# Bears_and_Bears_BLE_soil_Moisture_Sensor.net
KiCad netlist of a schematic drawn in EAGLE
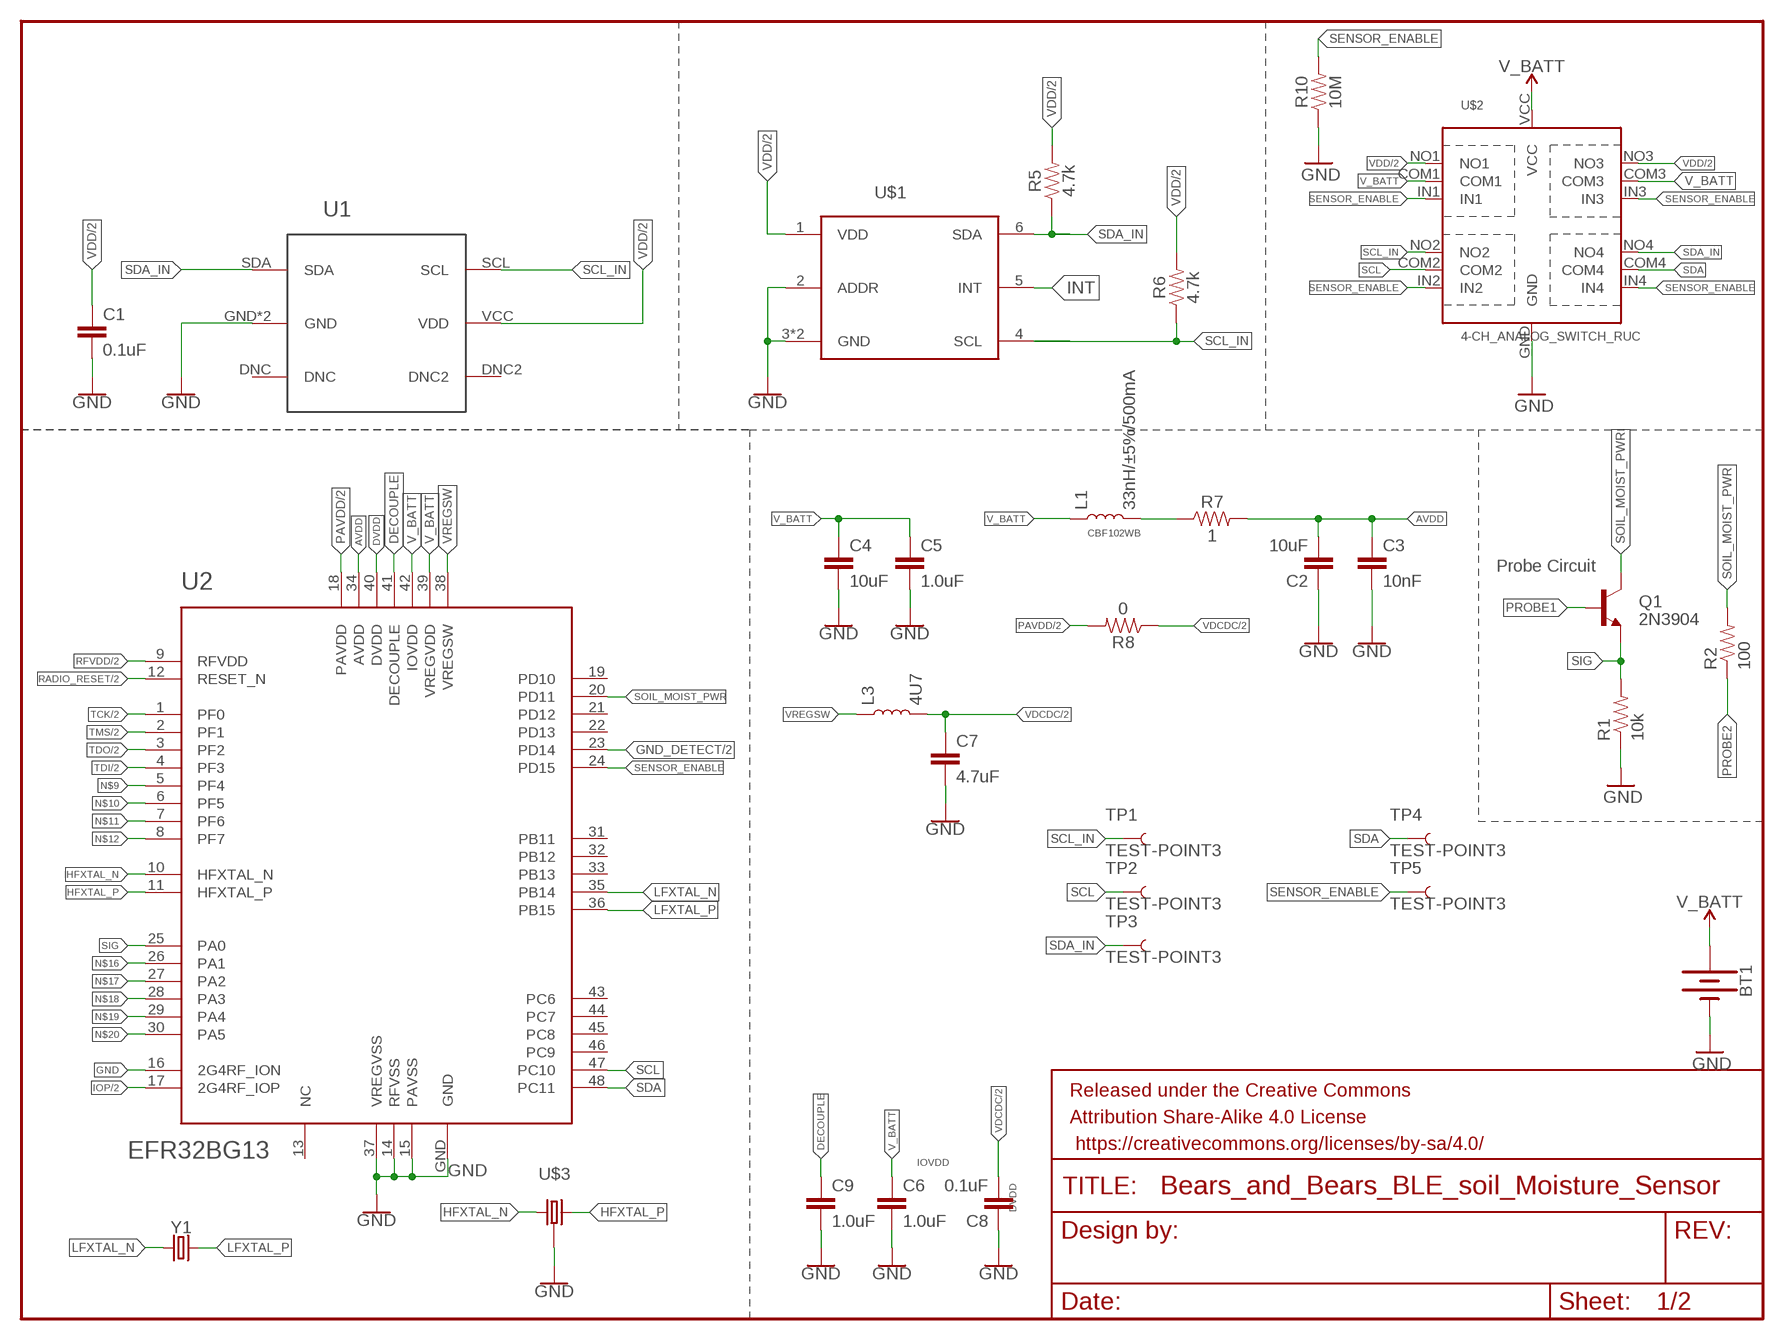
[diagram p0: schematic, sheet 1]
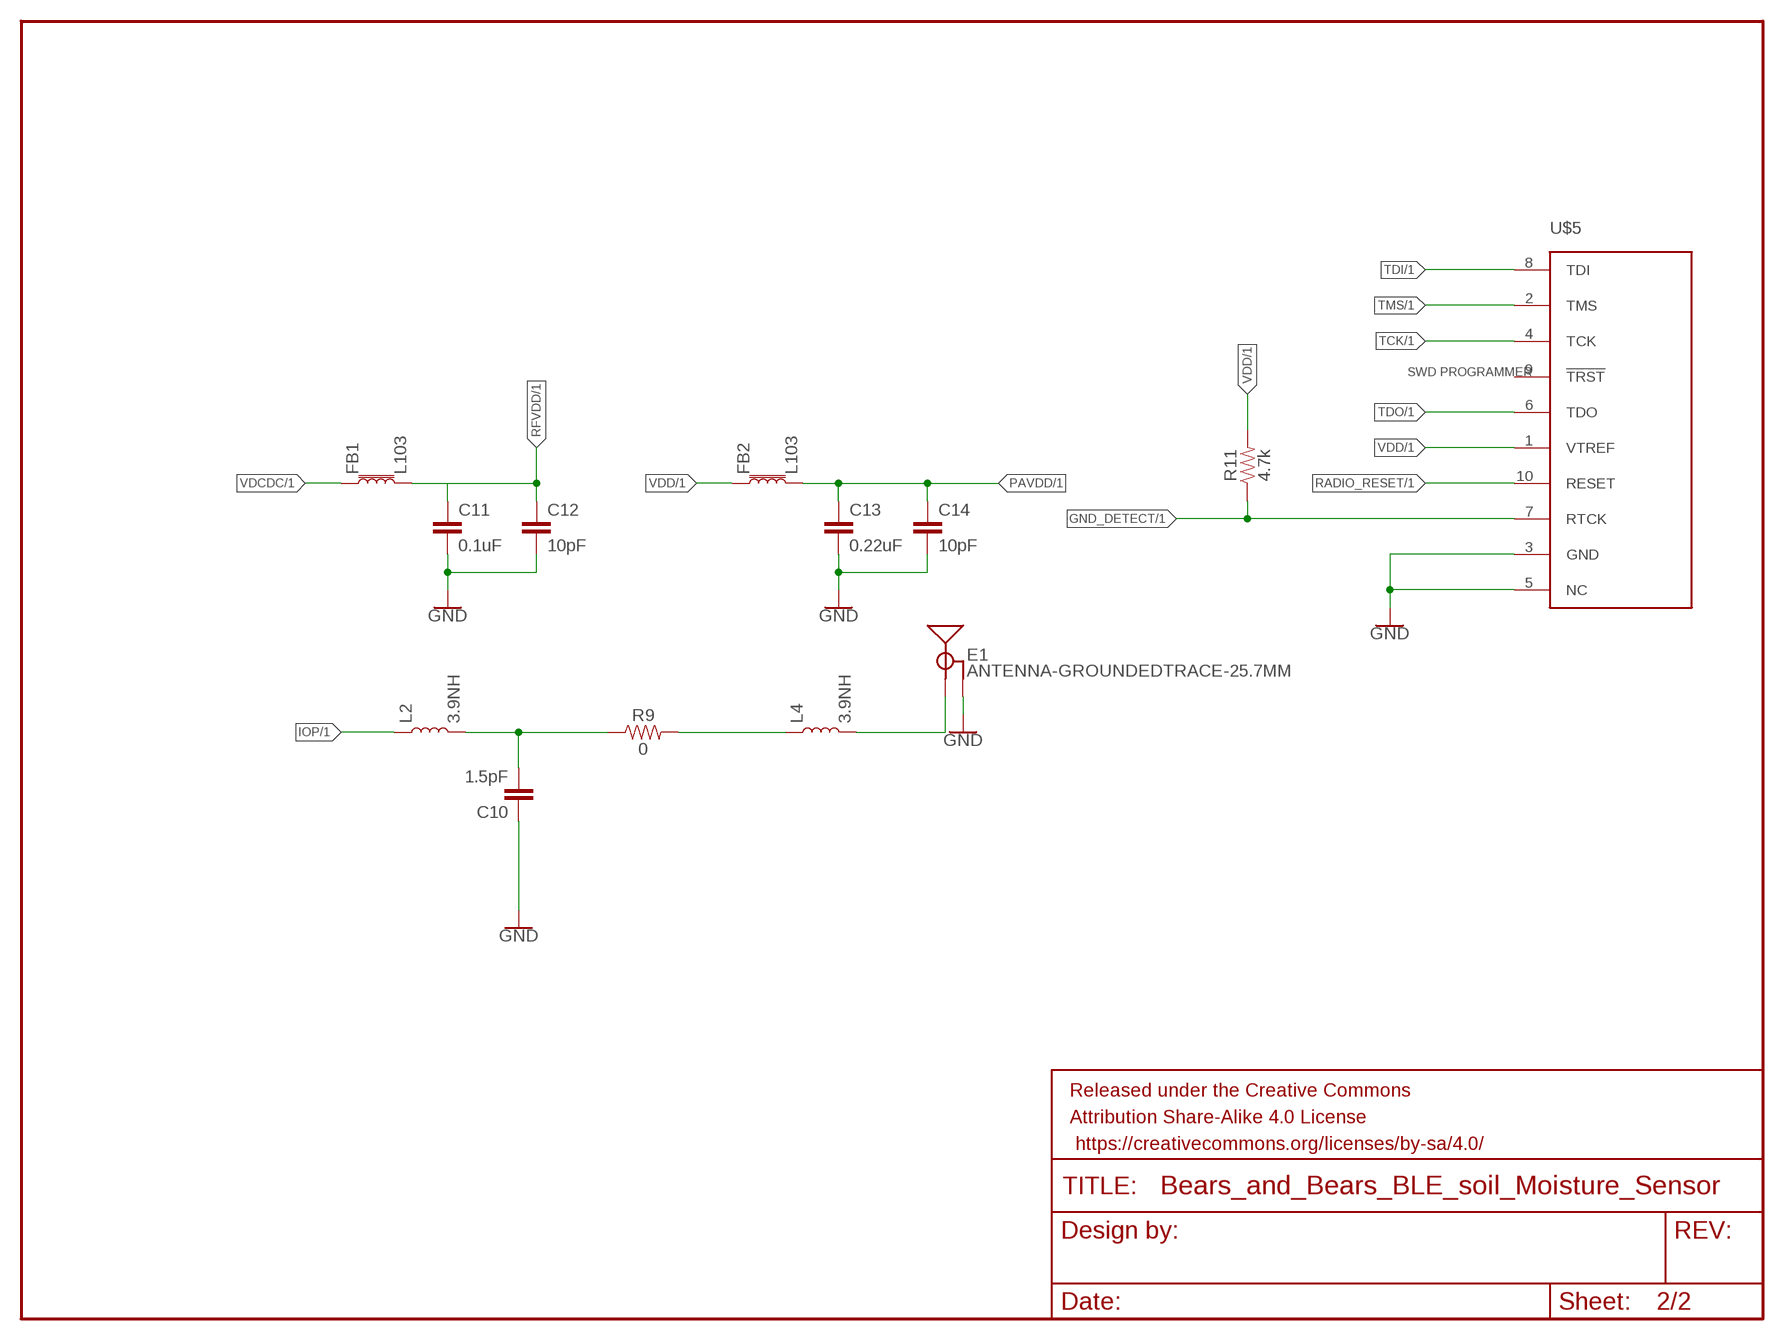
[diagram p1: schematic, sheet 2]

(export (version "E")
  (design (tool "Eeschema 10.0.6"))
  (components
    (comp (ref "BT1")
      (value "BATTERY-20MM_SMD_4LEGS_OVERPASTE")
      (footprint "eagle-import:BATTCON_20MM_4LEGS_OVERPASTE")
      (libsource (lib "eagle-import") (part "BATTERY-20MM_SMD_4LEGS_OVERPASTE"))
    )
    (comp (ref "C1")
      (value "0.1uF")
      (footprint "eagle-import:0603")
      (libsource (lib "eagle-import") (part "0.1UF-0603-25V-(+80/-20%)"))
    )
    (comp (ref "C2")
      (value "10uF")
      (footprint "eagle-import:0603")
      (libsource (lib "eagle-import") (part "10UF-0603-6.3V-20%"))
    )
    (comp (ref "C3")
      (value "10nF")
      (footprint "eagle-import:0603")
      (libsource (lib "eagle-import") (part "10NF-0603-50V-10%"))
    )
    (comp (ref "C4")
      (value "10uF")
      (footprint "eagle-import:0603")
      (libsource (lib "eagle-import") (part "10UF-0603-6.3V-20%"))
    )
    (comp (ref "C5")
      (value "1.0uF")
      (footprint "eagle-import:0603")
      (libsource (lib "eagle-import") (part "1.0UF-0603-16V-10%"))
    )
    (comp (ref "C6")
      (value "1.0uF")
      (footprint "eagle-import:0603")
      (libsource (lib "eagle-import") (part "1.0UF-0603-16V-10%"))
    )
    (comp (ref "C7")
      (value "4.7uF")
      (footprint "eagle-import:0603")
      (libsource (lib "eagle-import") (part "4.7UF0603"))
    )
    (comp (ref "C8")
      (value "0.1uF")
      (footprint "eagle-import:0603")
      (libsource (lib "eagle-import") (part "0.1UF-0603-25V-(+80/-20%)"))
    )
    (comp (ref "C9")
      (value "1.0uF")
      (footprint "eagle-import:0603")
      (libsource (lib "eagle-import") (part "1.0UF-0603-16V-10%"))
    )
    (comp (ref "FRAME1")
      (value "FRAME-LETTER")
      (footprint "eagle-import:CREATIVE_COMMONS")
      (libsource (lib "eagle-import") (part "FRAME-LETTER"))
    )
    (comp (ref "L1")
      (value "33nH/±5%/500mA")
      (footprint "eagle-import:0603")
      (libsource (lib "eagle-import") (part "INDUCTOR-0603-33NH"))
    )
    (comp (ref "L3")
      (value "4U7")
      (footprint "eagle-import:1212(3030METRIC)")
      (libsource (lib "eagle-import") (part "4U7"))
    )
    (comp (ref "Q1")
      (value "2N3904")
      (footprint "eagle-import:SOT23-3")
      (libsource (lib "eagle-import") (part "TRANSISTOR_NPNMMBT2222A"))
    )
    (comp (ref "R1")
      (value "10k")
      (footprint "eagle-import:0603-RES")
      (libsource (lib "eagle-import") (part "100OHM-1/4W-5%(0603)"))
    )
    (comp (ref "R2")
      (value "100")
      (footprint "eagle-import:0603-RES")
      (libsource (lib "eagle-import") (part "100OHM-1/4W-5%(0603)"))
    )
    (comp (ref "R5")
      (value "4.7k")
      (footprint "eagle-import:0603")
      (libsource (lib "eagle-import") (part "4.7KOHM-0603-1/10W-1%"))
    )
    (comp (ref "R6")
      (value "4.7k")
      (footprint "eagle-import:0603")
      (libsource (lib "eagle-import") (part "4.7KOHM-0603-1/10W-1%"))
    )
    (comp (ref "R7")
      (value "1")
      (footprint "eagle-import:0603")
      (libsource (lib "eagle-import") (part "1OHM-0603-1/10W-1%"))
    )
    (comp (ref "R8")
      (value "0")
      (footprint "eagle-import:0603")
      (libsource (lib "eagle-import") (part "0OHM-0603-1/10W-5%"))
    )
    (comp (ref "R10")
      (value "10M")
      (footprint "eagle-import:0603")
      (libsource (lib "eagle-import") (part "10MOHM-0603-1/10W-5%"))
    )
    (comp (ref "TP1")
      (value "TEST-POINT3")
      (footprint "eagle-import:PAD.03X.03")
      (libsource (lib "eagle-import") (part "TEST-POINT3"))
    )
    (comp (ref "TP2")
      (value "TEST-POINT3")
      (footprint "eagle-import:PAD.03X.03")
      (libsource (lib "eagle-import") (part "TEST-POINT3"))
    )
    (comp (ref "TP3")
      (value "TEST-POINT3")
      (footprint "eagle-import:PAD.03X.03")
      (libsource (lib "eagle-import") (part "TEST-POINT3"))
    )
    (comp (ref "TP4")
      (value "TEST-POINT3")
      (footprint "eagle-import:PAD.03X.03")
      (libsource (lib "eagle-import") (part "TEST-POINT3"))
    )
    (comp (ref "TP5")
      (value "TEST-POINT3")
      (footprint "eagle-import:PAD.03X.03")
      (libsource (lib "eagle-import") (part "TEST-POINT3"))
    )
    (comp (ref "U$1")
      (value "OPT3001DNPT")
      (footprint "eagle-import:6PIN_USON")
      (libsource (lib "eagle-import") (part "OPT3001DNPT"))
    )
    (comp (ref "U$2")
      (value "4-CH_ANALOG_SWITCH_RUC")
      (footprint "eagle-import:PX2QFN14_RUC")
      (libsource (lib "eagle-import") (part "4-CH_ANALOG_SWITCH_RUC"))
    )
    (comp (ref "U$3")
      (value "38.4MHZ_CRYSTAL")
      (footprint "eagle-import:2.0X1.6")
      (libsource (lib "eagle-import") (part "38.4MHZ_CRYSTAL"))
    )
    (comp (ref "U1")
      (value "SI7021_TEMP_HUMIDTY")
      (footprint "eagle-import:DFN-6")
      (libsource (lib "eagle-import") (part "SI7021_TEMP_HUMIDTY"))
    )
    (comp (ref "U2")
      (value "EFR32BG13")
      (footprint "eagle-import:QFN48")
      (libsource (lib "eagle-import") (part "EFR32BG13"))
    )
    (comp (ref "Y1")
      (value "32.768KHZ_LOW_FREQ_CRYSTAL")
      (footprint "eagle-import:CRYSTAL_1.2X0.6")
      (libsource (lib "eagle-import") (part "32.768KHZ_LOW_FREQ_CRYSTAL"))
    )
    (comp (ref "C10")
      (value "1.5pF")
      (footprint "eagle-import:0603")
      (libsource (lib "eagle-import") (part "1.5PF-0603-50V-16.667%"))
    )
    (comp (ref "C11")
      (value "0.1uF")
      (footprint "eagle-import:0603")
      (libsource (lib "eagle-import") (part "0.1UF-0603-25V-(+80/-20%)"))
    )
    (comp (ref "C12")
      (value "10pF")
      (footprint "eagle-import:0603")
      (libsource (lib "eagle-import") (part "10PF-0603-50V-5%"))
    )
    (comp (ref "C13")
      (value "0.22uF")
      (footprint "eagle-import:0603")
      (libsource (lib "eagle-import") (part "0.22UF-0603-25V-10%"))
    )
    (comp (ref "C14")
      (value "10pF")
      (footprint "eagle-import:0603")
      (libsource (lib "eagle-import") (part "10PF-0603-50V-5%"))
    )
    (comp (ref "E1")
      (value "ANTENNA-GROUNDEDTRACE-25.7MM")
      (footprint "eagle-import:TRACE_ANTENNA_2.4GHZ_25.7MM")
      (libsource (lib "eagle-import") (part "ANTENNA-GROUNDEDTRACE-25.7MM"))
    )
    (comp (ref "FB1")
      (value "L103")
      (footprint "eagle-import:0603")
      (libsource (lib "eagle-import") (part "FERRITE_BEAD-0603"))
    )
    (comp (ref "FB2")
      (value "L103")
      (footprint "eagle-import:0603")
      (libsource (lib "eagle-import") (part "FERRITE_BEAD-0603"))
    )
    (comp (ref "FRAME2")
      (value "FRAME-LETTER")
      (footprint "eagle-import:CREATIVE_COMMONS")
      (libsource (lib "eagle-import") (part "FRAME-LETTER"))
    )
    (comp (ref "L2")
      (value "3.9NH")
      (footprint "eagle-import:0402")
      (libsource (lib "eagle-import") (part "INDUCTOR-0402-3.9NH"))
    )
    (comp (ref "L4")
      (value "3.9NH")
      (footprint "eagle-import:0402")
      (libsource (lib "eagle-import") (part "INDUCTOR-0402-3.9NH"))
    )
    (comp (ref "R9")
      (value "0")
      (footprint "eagle-import:0805")
      (libsource (lib "eagle-import") (part "0.22OHM-0805-1/4W-1%"))
    )
    (comp (ref "R11")
      (value "4.7k")
      (footprint "eagle-import:0603")
      (libsource (lib "eagle-import") (part "4.7KOHM-0603-1/10W-1%"))
    )
    (comp (ref "U$5")
      (value "TC2050-MCP-NL")
      (footprint "eagle-import:TC2030-MCP-NL")
      (libsource (lib "eagle-import") (part "TC2050-MCP-NL"))
    )
  )
  (nets
    (net (code "1") (name "AVDD") (class "Default")
      (node (ref "C2") (pin "2") (pinfunction "2_2") (pintype "passive"))
      (node (ref "C3") (pin "1") (pinfunction "1_1") (pintype "passive"))
      (node (ref "R7") (pin "2") (pinfunction "2_2") (pintype "passive"))
      (node (ref "U2") (pin "34") (pinfunction "AVDD_34") (pintype "bidirectional"))
    )
    (net (code "2") (name "DECOUPLE") (class "Default")
      (node (ref "C9") (pin "1") (pinfunction "1_1") (pintype "passive"))
      (node (ref "U2") (pin "41") (pinfunction "DECOUPLE_41") (pintype "bidirectional"))
    )
    (net (code "3") (name "DVDD") (class "Default")
      (node (ref "U2") (pin "40") (pinfunction "DVDD_40") (pintype "bidirectional"))
    )
    (net (code "4") (name "GND") (class "Default")
      (node (ref "BT1") (pin "2") (pinfunction "-_2") (pintype "power_in"))
      (node (ref "C1") (pin "2") (pinfunction "2_2") (pintype "passive"))
      (node (ref "C10") (pin "1") (pinfunction "1_1") (pintype "passive"))
      (node (ref "C11") (pin "2") (pinfunction "2_2") (pintype "passive"))
      (node (ref "C12") (pin "2") (pinfunction "2_2") (pintype "passive"))
      (node (ref "C13") (pin "2") (pinfunction "2_2") (pintype "passive"))
      (node (ref "C14") (pin "2") (pinfunction "2_2") (pintype "passive"))
      (node (ref "C2") (pin "1") (pinfunction "1_1") (pintype "passive"))
      (node (ref "C3") (pin "2") (pinfunction "2_2") (pintype "passive"))
      (node (ref "C4") (pin "2") (pinfunction "2_2") (pintype "passive"))
      (node (ref "C5") (pin "2") (pinfunction "2_2") (pintype "passive"))
      (node (ref "C6") (pin "2") (pinfunction "2_2") (pintype "passive"))
      (node (ref "C7") (pin "2") (pinfunction "2_2") (pintype "passive"))
      (node (ref "C8") (pin "1") (pinfunction "1_1") (pintype "passive"))
      (node (ref "C9") (pin "2") (pinfunction "2_2") (pintype "passive"))
      (node (ref "E1") (pin "GND") (pinfunction "GND_GND") (pintype "bidirectional"))
      (node (ref "E1") (pin "GND2") (pinfunction "GND_GND2") (pintype "bidirectional"))
      (node (ref "R1") (pin "1") (pinfunction "1_1") (pintype "passive"))
      (node (ref "R10") (pin "1") (pinfunction "1_1") (pintype "passive"))
      (node (ref "U$1") (pin "2") (pinfunction "ADDR_2") (pintype "bidirectional"))
      (node (ref "U$1") (pin "3") (pinfunction "GND_3") (pintype "bidirectional"))
      (node (ref "U$1") (pin "GND") (pinfunction "GND_GND") (pintype "bidirectional"))
      (node (ref "U$2") (pin "GND") (pinfunction "GND_GND") (pintype "bidirectional"))
      (node (ref "U$3") (pin "GND") (pinfunction "GND_GND") (pintype "bidirectional"))
      (node (ref "U$3") (pin "GND2") (pinfunction "GND_GND2") (pintype "bidirectional"))
      (node (ref "U$5") (pin "3") (pinfunction "GND_3") (pintype "bidirectional"))
      (node (ref "U$5") (pin "5") (pinfunction "NC_5") (pintype "bidirectional"))
      (node (ref "U1") (pin "GND") (pinfunction "GND_GND") (pintype "bidirectional"))
      (node (ref "U1") (pin "GND2") (pinfunction "GND_GND2") (pintype "bidirectional"))
      (node (ref "U2") (pin "14") (pinfunction "RFVSS_14") (pintype "bidirectional"))
      (node (ref "U2") (pin "15") (pinfunction "PAVSS_15") (pintype "bidirectional"))
      (node (ref "U2") (pin "16") (pinfunction "2G4RF_ION_16") (pintype "bidirectional"))
      (node (ref "U2") (pin "37") (pinfunction "VREGVSS_37") (pintype "bidirectional"))
      (node (ref "U2") (pin "GND") (pinfunction "GND_GND") (pintype "bidirectional"))
    )
    (net (code "5") (name "GND_DETECT") (class "Default")
      (node (ref "R11") (pin "1") (pinfunction "1_1") (pintype "passive"))
      (node (ref "U$5") (pin "7") (pinfunction "RTCK_7") (pintype "bidirectional"))
      (node (ref "U2") (pin "23") (pinfunction "PD14_23") (pintype "bidirectional"))
    )
    (net (code "6") (name "HFXTAL_N") (class "Default")
      (node (ref "U$3") (pin "1") (pinfunction "1_1") (pintype "passive"))
      (node (ref "U2") (pin "10") (pinfunction "HFXTAL_N_10") (pintype "bidirectional"))
    )
    (net (code "7") (name "HFXTAL_P") (class "Default")
      (node (ref "U$3") (pin "3") (pinfunction "2_3") (pintype "passive"))
      (node (ref "U2") (pin "11") (pinfunction "HFXTAL_P_11") (pintype "bidirectional"))
    )
    (net (code "8") (name "INT") (class "Default")
      (node (ref "U$1") (pin "5") (pinfunction "INT_5") (pintype "bidirectional"))
    )
    (net (code "9") (name "IOP") (class "Default")
      (node (ref "L2") (pin "1") (pinfunction "1_1") (pintype "passive"))
      (node (ref "U2") (pin "17") (pinfunction "2G4RF_IOP_17") (pintype "bidirectional"))
    )
    (net (code "10") (name "LFXTAL_N") (class "Default")
      (node (ref "U2") (pin "35") (pinfunction "PB14_35") (pintype "bidirectional"))
      (node (ref "Y1") (pin "P$1") (pinfunction "1_P$1") (pintype "passive"))
    )
    (net (code "11") (name "LFXTAL_P") (class "Default")
      (node (ref "U2") (pin "36") (pinfunction "PB15_36") (pintype "bidirectional"))
      (node (ref "Y1") (pin "P$2") (pinfunction "2_P$2") (pintype "passive"))
    )
    (net (code "12") (name "N$9") (class "Default")
      (node (ref "U2") (pin "5") (pinfunction "PF4_5") (pintype "bidirectional"))
    )
    (net (code "13") (name "N$10") (class "Default")
      (node (ref "U2") (pin "6") (pinfunction "PF5_6") (pintype "bidirectional"))
    )
    (net (code "14") (name "N$11") (class "Default")
      (node (ref "U2") (pin "7") (pinfunction "PF6_7") (pintype "bidirectional"))
    )
    (net (code "15") (name "N$12") (class "Default")
      (node (ref "U2") (pin "8") (pinfunction "PF7_8") (pintype "bidirectional"))
    )
    (net (code "16") (name "N$16") (class "Default")
      (node (ref "U2") (pin "26") (pinfunction "PA1_26") (pintype "bidirectional"))
    )
    (net (code "17") (name "N$17") (class "Default")
      (node (ref "U2") (pin "27") (pinfunction "PA2_27") (pintype "bidirectional"))
    )
    (net (code "18") (name "N$18") (class "Default")
      (node (ref "U2") (pin "28") (pinfunction "PA3_28") (pintype "bidirectional"))
    )
    (net (code "19") (name "N$19") (class "Default")
      (node (ref "U2") (pin "29") (pinfunction "PA4_29") (pintype "bidirectional"))
    )
    (net (code "20") (name "N$20") (class "Default")
      (node (ref "U2") (pin "30") (pinfunction "PA5_30") (pintype "bidirectional"))
    )
    (net (code "21") (name "Net-(C10-Pad2)") (class "Default")
      (node (ref "C10") (pin "2") (pinfunction "2_2") (pintype "passive"))
      (node (ref "L2") (pin "2") (pinfunction "2_2") (pintype "passive"))
      (node (ref "R9") (pin "1") (pinfunction "1_1") (pintype "passive"))
    )
    (net (code "22") (name "Net-(E1-SIGNAL)") (class "Default")
      (node (ref "E1") (pin "ANT") (pinfunction "SIGNAL_ANT") (pintype "bidirectional"))
      (node (ref "L4") (pin "2") (pinfunction "2_2") (pintype "passive"))
    )
    (net (code "23") (name "Net-(L1-Pad2)") (class "Default")
      (node (ref "L1") (pin "2") (pinfunction "2_2") (pintype "passive"))
      (node (ref "R7") (pin "1") (pinfunction "1_1") (pintype "passive"))
    )
    (net (code "24") (name "Net-(L4-Pad1)") (class "Default")
      (node (ref "L4") (pin "1") (pinfunction "1_1") (pintype "passive"))
      (node (ref "R9") (pin "2") (pinfunction "2_2") (pintype "passive"))
    )
    (net (code "25") (name "PAVDD") (class "Default")
      (node (ref "C13") (pin "1") (pinfunction "1_1") (pintype "passive"))
      (node (ref "C14") (pin "1") (pinfunction "1_1") (pintype "passive"))
      (node (ref "FB2") (pin "2") (pinfunction "2_2") (pintype "passive"))
      (node (ref "R8") (pin "2") (pinfunction "2_2") (pintype "passive"))
      (node (ref "U2") (pin "18") (pinfunction "PAVDD_18") (pintype "bidirectional"))
    )
    (net (code "26") (name "PROBE1") (class "Default")
      (node (ref "Q1") (pin "1") (pinfunction "B_1") (pintype "passive"))
    )
    (net (code "27") (name "PROBE2") (class "Default")
      (node (ref "R2") (pin "1") (pinfunction "1_1") (pintype "passive"))
    )
    (net (code "28") (name "RADIO_RESET") (class "Default")
      (node (ref "U$5") (pin "10") (pinfunction "RESET_10") (pintype "bidirectional"))
      (node (ref "U2") (pin "12") (pinfunction "RESET_N_12") (pintype "bidirectional"))
    )
    (net (code "29") (name "RFVDD") (class "Default")
      (node (ref "C11") (pin "1") (pinfunction "1_1") (pintype "passive"))
      (node (ref "C12") (pin "1") (pinfunction "1_1") (pintype "passive"))
      (node (ref "FB1") (pin "2") (pinfunction "2_2") (pintype "passive"))
      (node (ref "U2") (pin "9") (pinfunction "RFVDD_9") (pintype "bidirectional"))
    )
    (net (code "30") (name "SCL") (class "Default")
      (node (ref "TP2") (pin "P$1") (pinfunction "1_P$1") (pintype "bidirectional"))
      (node (ref "U$2") (pin "COM2") (pinfunction "COM2_COM2") (pintype "bidirectional"))
      (node (ref "U2") (pin "47") (pinfunction "PC10_47") (pintype "bidirectional"))
    )
    (net (code "31") (name "SCL_IN") (class "Default")
      (node (ref "R6") (pin "1") (pinfunction "1_1") (pintype "passive"))
      (node (ref "TP1") (pin "P$1") (pinfunction "1_P$1") (pintype "bidirectional"))
      (node (ref "U$1") (pin "4") (pinfunction "SCL_4") (pintype "bidirectional"))
      (node (ref "U$2") (pin "NO2") (pinfunction "NO2_NO2") (pintype "bidirectional"))
      (node (ref "U1") (pin "SCL") (pinfunction "SCL_SCL") (pintype "bidirectional"))
    )
    (net (code "32") (name "SDA") (class "Default")
      (node (ref "TP4") (pin "P$1") (pinfunction "1_P$1") (pintype "bidirectional"))
      (node (ref "U$2") (pin "COM4") (pinfunction "COM4_COM4") (pintype "bidirectional"))
      (node (ref "U2") (pin "48") (pinfunction "PC11_48") (pintype "bidirectional"))
    )
    (net (code "33") (name "SDA_IN") (class "Default")
      (node (ref "R5") (pin "1") (pinfunction "1_1") (pintype "passive"))
      (node (ref "TP3") (pin "P$1") (pinfunction "1_P$1") (pintype "bidirectional"))
      (node (ref "U$1") (pin "6") (pinfunction "SDA_6") (pintype "bidirectional"))
      (node (ref "U$2") (pin "NO4") (pinfunction "NO4_NO4") (pintype "bidirectional"))
      (node (ref "U1") (pin "SDA") (pinfunction "SDA_SDA") (pintype "bidirectional"))
    )
    (net (code "34") (name "SENSOR_ENABLE") (class "Default")
      (node (ref "R10") (pin "2") (pinfunction "2_2") (pintype "passive"))
      (node (ref "TP5") (pin "P$1") (pinfunction "1_P$1") (pintype "bidirectional"))
      (node (ref "U$2") (pin "IN1") (pinfunction "IN1_IN1") (pintype "bidirectional"))
      (node (ref "U$2") (pin "IN2") (pinfunction "IN2_IN2") (pintype "bidirectional"))
      (node (ref "U$2") (pin "IN3") (pinfunction "IN3_IN3") (pintype "bidirectional"))
      (node (ref "U$2") (pin "IN4") (pinfunction "IN4_IN4") (pintype "bidirectional"))
      (node (ref "U2") (pin "24") (pinfunction "PD15_24") (pintype "bidirectional"))
    )
    (net (code "35") (name "SIG") (class "Default")
      (node (ref "Q1") (pin "2") (pinfunction "E_2") (pintype "passive"))
      (node (ref "R1") (pin "2") (pinfunction "2_2") (pintype "passive"))
      (node (ref "U2") (pin "25") (pinfunction "PA0_25") (pintype "bidirectional"))
    )
    (net (code "36") (name "SOIL_MOIST_PWR") (class "Default")
      (node (ref "Q1") (pin "3") (pinfunction "C_3") (pintype "passive"))
      (node (ref "R2") (pin "2") (pinfunction "2_2") (pintype "passive"))
      (node (ref "U2") (pin "20") (pinfunction "PD11_20") (pintype "bidirectional"))
    )
    (net (code "37") (name "TCK") (class "Default")
      (node (ref "U$5") (pin "4") (pinfunction "TCK_4") (pintype "bidirectional"))
      (node (ref "U2") (pin "1") (pinfunction "PF0_1") (pintype "bidirectional"))
    )
    (net (code "38") (name "TDI") (class "Default")
      (node (ref "U$5") (pin "8") (pinfunction "TDI_8") (pintype "bidirectional"))
      (node (ref "U2") (pin "4") (pinfunction "PF3_4") (pintype "bidirectional"))
    )
    (net (code "39") (name "TDO") (class "Default")
      (node (ref "U$5") (pin "6") (pinfunction "TDO_6") (pintype "bidirectional"))
      (node (ref "U2") (pin "3") (pinfunction "PF2_3") (pintype "bidirectional"))
    )
    (net (code "40") (name "TMS") (class "Default")
      (node (ref "U$5") (pin "2") (pinfunction "TMS_2") (pintype "bidirectional"))
      (node (ref "U2") (pin "2") (pinfunction "PF1_2") (pintype "bidirectional"))
    )
    (net (code "41") (name "VDCDC") (class "Default")
      (node (ref "C7") (pin "1") (pinfunction "1_1") (pintype "passive"))
      (node (ref "C8") (pin "2") (pinfunction "2_2") (pintype "passive"))
      (node (ref "FB1") (pin "1") (pinfunction "1_1") (pintype "passive"))
      (node (ref "L3") (pin "P$2") (pinfunction "2_P$2") (pintype "passive"))
      (node (ref "R8") (pin "1") (pinfunction "1_1") (pintype "passive"))
    )
    (net (code "42") (name "VDD") (class "Default")
      (node (ref "C1") (pin "1") (pinfunction "1_1") (pintype "passive"))
      (node (ref "FB2") (pin "1") (pinfunction "1_1") (pintype "passive"))
      (node (ref "R11") (pin "2") (pinfunction "2_2") (pintype "passive"))
      (node (ref "R5") (pin "2") (pinfunction "2_2") (pintype "passive"))
      (node (ref "R6") (pin "2") (pinfunction "2_2") (pintype "passive"))
      (node (ref "U$1") (pin "1") (pinfunction "VDD_1") (pintype "bidirectional"))
      (node (ref "U$2") (pin "NO1") (pinfunction "NO1_NO1") (pintype "bidirectional"))
      (node (ref "U$2") (pin "NO3") (pinfunction "NO3_NO3") (pintype "bidirectional"))
      (node (ref "U$5") (pin "1") (pinfunction "VTREF_1") (pintype "bidirectional"))
      (node (ref "U1") (pin "VCC") (pinfunction "VDD_VCC") (pintype "bidirectional"))
    )
    (net (code "43") (name "VREGSW") (class "Default")
      (node (ref "L3") (pin "P$1") (pinfunction "1_P$1") (pintype "passive"))
      (node (ref "U2") (pin "38") (pinfunction "VREGSW_38") (pintype "bidirectional"))
    )
    (net (code "44") (name "V_BATT") (class "Default")
      (node (ref "BT1") (pin "1") (pinfunction "+_1") (pintype "power_in"))
      (node (ref "C4") (pin "1") (pinfunction "1_1") (pintype "passive"))
      (node (ref "C5") (pin "1") (pinfunction "1_1") (pintype "passive"))
      (node (ref "C6") (pin "1") (pinfunction "1_1") (pintype "passive"))
      (node (ref "L1") (pin "1") (pinfunction "1_1") (pintype "passive"))
      (node (ref "U$2") (pin "COM1") (pinfunction "COM1_COM1") (pintype "bidirectional"))
      (node (ref "U$2") (pin "COM3") (pinfunction "COM3_COM3") (pintype "bidirectional"))
      (node (ref "U$2") (pin "VCC") (pinfunction "VCC_VCC") (pintype "bidirectional"))
      (node (ref "U2") (pin "39") (pinfunction "VREGVDD_39") (pintype "bidirectional"))
      (node (ref "U2") (pin "42") (pinfunction "IOVDD_42") (pintype "bidirectional"))
    )
    (net (code "45") (name "unconnected-(U$5-~{TRST}-Pad9)") (class "Default")
      (node (ref "U$5") (pin "9") (pinfunction "~{TRST}_9") (pintype "bidirectional"))
    )
    (net (code "46") (name "unconnected-(U1-PadDNC)") (class "Default")
      (node (ref "U1") (pin "DNC") (pinfunction "DNC_DNC") (pintype "bidirectional"))
    )
    (net (code "47") (name "unconnected-(U1-PadDNC2)") (class "Default")
      (node (ref "U1") (pin "DNC2") (pinfunction "DNC2_DNC2") (pintype "bidirectional"))
    )
    (net (code "48") (name "unconnected-(U2-NC-Pad13)") (class "Default")
      (node (ref "U2") (pin "13") (pinfunction "NC_13") (pintype "bidirectional"))
    )
    (net (code "49") (name "unconnected-(U2-PB11-Pad31)") (class "Default")
      (node (ref "U2") (pin "31") (pinfunction "PB11_31") (pintype "bidirectional"))
    )
    (net (code "50") (name "unconnected-(U2-PB12-Pad32)") (class "Default")
      (node (ref "U2") (pin "32") (pinfunction "PB12_32") (pintype "bidirectional"))
    )
    (net (code "51") (name "unconnected-(U2-PB13-Pad33)") (class "Default")
      (node (ref "U2") (pin "33") (pinfunction "PB13_33") (pintype "bidirectional"))
    )
    (net (code "52") (name "unconnected-(U2-PC6-Pad43)") (class "Default")
      (node (ref "U2") (pin "43") (pinfunction "PC6_43") (pintype "bidirectional"))
    )
    (net (code "53") (name "unconnected-(U2-PC7-Pad44)") (class "Default")
      (node (ref "U2") (pin "44") (pinfunction "PC7_44") (pintype "bidirectional"))
    )
    (net (code "54") (name "unconnected-(U2-PC8-Pad45)") (class "Default")
      (node (ref "U2") (pin "45") (pinfunction "PC8_45") (pintype "bidirectional"))
    )
    (net (code "55") (name "unconnected-(U2-PC9-Pad46)") (class "Default")
      (node (ref "U2") (pin "46") (pinfunction "PC9_46") (pintype "bidirectional"))
    )
    (net (code "56") (name "unconnected-(U2-PD10-Pad19)") (class "Default")
      (node (ref "U2") (pin "19") (pinfunction "PD10_19") (pintype "bidirectional"))
    )
    (net (code "57") (name "unconnected-(U2-PD12-Pad21)") (class "Default")
      (node (ref "U2") (pin "21") (pinfunction "PD12_21") (pintype "bidirectional"))
    )
    (net (code "58") (name "unconnected-(U2-PD13-Pad22)") (class "Default")
      (node (ref "U2") (pin "22") (pinfunction "PD13_22") (pintype "bidirectional"))
    )
  )
)
